# main.net
KiCad netlist of a schematic drawn in EAGLE
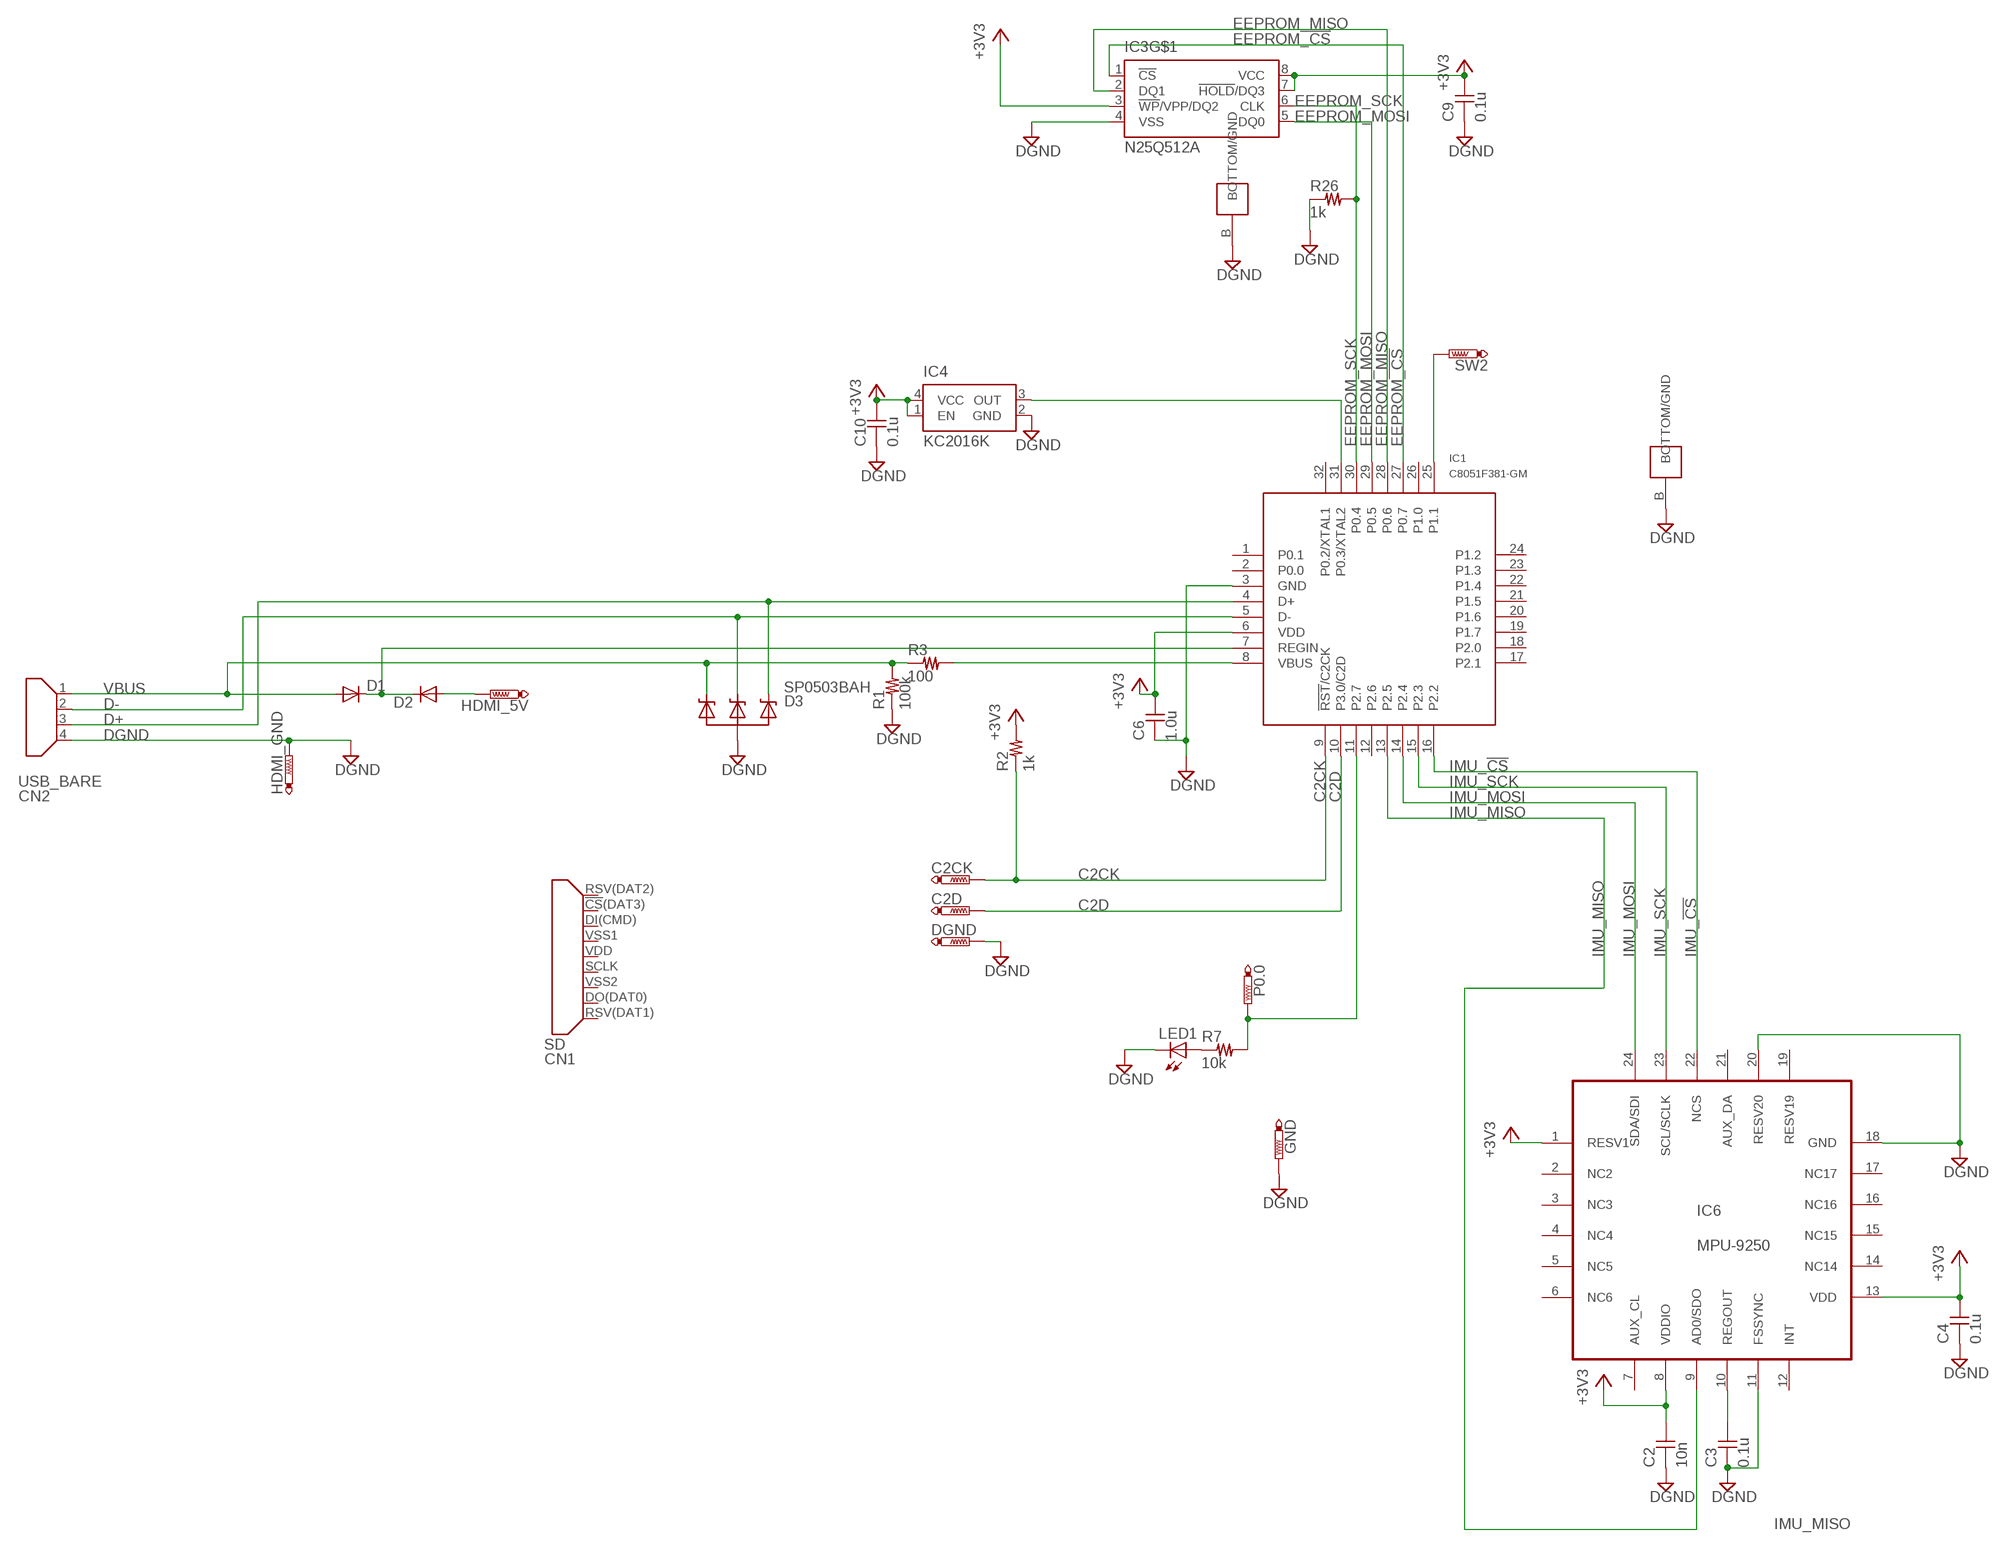
[diagram p0: schematic, sheet 1]

(export (version "E")
  (design (tool "Eeschema 10.0.6"))
  (components
    (comp (ref "C2")
      (value "10n")
      (footprint "eagle-import:1005")
      (libsource (lib "eagle-import") (part "C-1005"))
    )
    (comp (ref "C2CK")
      (value "PTR1TP10R")
      (footprint "eagle-import:TP10R")
      (libsource (lib "eagle-import") (part "PTR1TP10R"))
    )
    (comp (ref "C2D")
      (value "PTR1TP10R")
      (footprint "eagle-import:TP10R")
      (libsource (lib "eagle-import") (part "PTR1TP10R"))
    )
    (comp (ref "C3")
      (value "0.1u")
      (footprint "eagle-import:1005")
      (libsource (lib "eagle-import") (part "C-1005"))
    )
    (comp (ref "C4")
      (value "0.1u")
      (footprint "eagle-import:1005")
      (libsource (lib "eagle-import") (part "C-1005"))
    )
    (comp (ref "C6")
      (value "1.0u")
      (footprint "eagle-import:1005")
      (libsource (lib "eagle-import") (part "C-1005"))
    )
    (comp (ref "C9")
      (value "0.1u")
      (footprint "eagle-import:1005")
      (libsource (lib "eagle-import") (part "C-1005"))
    )
    (comp (ref "C10")
      (value "0.1u")
      (footprint "eagle-import:1005")
      (libsource (lib "eagle-import") (part "C-1005"))
    )
    (comp (ref "CN1") (value "SD") (footprint "eagle-import:SD") (libsource (lib "eagle-import") (part "SD")))
    (comp (ref "CN2")
      (value "USB_BARE")
      (footprint "eagle-import:USB_BARE")
      (libsource (lib "eagle-import") (part "USB_BARE"))
    )
    (comp (ref "D1")
      (value "DIODE-SOD323-W")
      (footprint "eagle-import:SOD323-W")
      (libsource (lib "eagle-import") (part "DIODE-SOD323-W"))
    )
    (comp (ref "D2")
      (value "DIODE-SOD323-W")
      (footprint "eagle-import:SOD323-W")
      (libsource (lib "eagle-import") (part "DIODE-SOD323-W"))
    )
    (comp (ref "D3")
      (value "SP0503BAH")
      (footprint "eagle-import:SOT143")
      (libsource (lib "eagle-import") (part "SP0503BAH"))
    )
    (comp (ref "DGND")
      (value "PTR1TP10R")
      (footprint "eagle-import:TP10R")
      (libsource (lib "eagle-import") (part "PTR1TP10R"))
    )
    (comp (ref "GND")
      (value "PTR1TP10R")
      (footprint "eagle-import:TP10R")
      (libsource (lib "eagle-import") (part "PTR1TP10R"))
    )
    (comp (ref "HDMI_5V")
      (value "PTR1TP11R")
      (footprint "eagle-import:TP11R")
      (libsource (lib "eagle-import") (part "PTR1TP11R"))
    )
    (comp (ref "HDMI_GND")
      (value "PTR1TP11R")
      (footprint "eagle-import:TP11R")
      (libsource (lib "eagle-import") (part "PTR1TP11R"))
    )
    (comp (ref "IC1")
      (value "C8051F381-GM")
      (footprint "eagle-import:QFN32")
      (libsource (lib "eagle-import") (part "C8051F381-GM"))
    )
    (comp (ref "IC3")
      (value "N25Q512A")
      (footprint "eagle-import:V-PDFN-8")
      (libsource (lib "eagle-import") (part "N25Q512A"))
    )
    (comp (ref "IC4")
      (value "KC2016K")
      (footprint "eagle-import:KC2016K")
      (libsource (lib "eagle-import") (part "KC2016K"))
    )
    (comp (ref "IC6")
      (value "MPU-9250")
      (footprint "eagle-import:QFN-24")
      (libsource (lib "eagle-import") (part "MPU-9250"))
    )
    (comp (ref "LED1")
      (value "LED1608O")
      (footprint "eagle-import:1608-OLI")
      (libsource (lib "eagle-import") (part "LED1608O"))
    )
    (comp (ref "P0.0")
      (value "PTR1TP10R")
      (footprint "eagle-import:TP10R")
      (libsource (lib "eagle-import") (part "PTR1TP10R"))
    )
    (comp (ref "R1")
      (value "100k")
      (footprint "eagle-import:1005")
      (libsource (lib "eagle-import") (part "R-1005"))
    )
    (comp (ref "R2")
      (value "1k")
      (footprint "eagle-import:1005")
      (libsource (lib "eagle-import") (part "R-1005"))
    )
    (comp (ref "R3")
      (value "100")
      (footprint "eagle-import:1005")
      (libsource (lib "eagle-import") (part "R-1005"))
    )
    (comp (ref "R7")
      (value "10k")
      (footprint "eagle-import:1005")
      (libsource (lib "eagle-import") (part "R-1005"))
    )
    (comp (ref "R26")
      (value "1k")
      (footprint "eagle-import:1005")
      (libsource (lib "eagle-import") (part "R-1005"))
    )
    (comp (ref "SW2")
      (value "PTR1TP10R")
      (footprint "eagle-import:TP10R")
      (libsource (lib "eagle-import") (part "PTR1TP10R"))
    )
  )
  (nets
    (net (code "1") (name "+3V3") (class "Default")
      (node (ref "C10") (pin "P$2") (pinfunction "P$2_P$2") (pintype "passive"))
      (node (ref "C2") (pin "P$2") (pinfunction "P$2_P$2") (pintype "passive"))
      (node (ref "C4") (pin "P$2") (pinfunction "P$2_P$2") (pintype "passive"))
      (node (ref "C6") (pin "P$2") (pinfunction "P$2_P$2") (pintype "passive"))
      (node (ref "C9") (pin "P$2") (pinfunction "P$2_P$2") (pintype "passive"))
      (node (ref "IC1") (pin "6") (pinfunction "VDD_6") (pintype "bidirectional"))
      (node (ref "IC3") (pin "3") (pinfunction "~{WP}/VPP/DQ2_3") (pintype "bidirectional"))
      (node (ref "IC3") (pin "7") (pinfunction "~{HOLD}/DQ3_7") (pintype "bidirectional"))
      (node (ref "IC3") (pin "8") (pinfunction "VCC_8") (pintype "power_in"))
      (node (ref "IC4") (pin "1") (pinfunction "EN_1") (pintype "input"))
      (node (ref "IC4") (pin "4") (pinfunction "VCC_4") (pintype "power_in"))
      (node (ref "IC6") (pin "1") (pinfunction "RESV1_1") (pintype "input"))
      (node (ref "IC6") (pin "13") (pinfunction "VDD_13") (pintype "power_in"))
      (node (ref "IC6") (pin "8") (pinfunction "VDDIO_8") (pintype "power_in"))
      (node (ref "R2") (pin "P$2") (pinfunction "P$2_P$2") (pintype "passive"))
    )
    (net (code "2") (name "/C2CK") (class "Default")
      (node (ref "C2CK") (pin "TP") (pinfunction "TP_TP") (pintype "input"))
      (node (ref "IC1") (pin "9") (pinfunction "~{RST}/C2CK_9") (pintype "bidirectional"))
      (node (ref "R2") (pin "P$1") (pinfunction "P$1_P$1") (pintype "passive"))
    )
    (net (code "3") (name "/C2D") (class "Default")
      (node (ref "C2D") (pin "TP") (pinfunction "TP_TP") (pintype "input"))
      (node (ref "IC1") (pin "10") (pinfunction "P3.0/C2D_10") (pintype "bidirectional"))
    )
    (net (code "4") (name "/D+") (class "Default")
      (node (ref "CN2") (pin "3") (pinfunction "P$3_3") (pintype "passive"))
      (node (ref "D3") (pin "2") (pinfunction "2_2") (pintype "passive"))
      (node (ref "IC1") (pin "4") (pinfunction "D+_4") (pintype "bidirectional"))
    )
    (net (code "5") (name "/D-") (class "Default")
      (node (ref "CN2") (pin "2") (pinfunction "P$2_2") (pintype "passive"))
      (node (ref "D3") (pin "3") (pinfunction "3_3") (pintype "passive"))
      (node (ref "IC1") (pin "5") (pinfunction "D-_5") (pintype "bidirectional"))
    )
    (net (code "6") (name "/EEPROM_MISO") (class "Default")
      (node (ref "IC1") (pin "28") (pinfunction "P0.6_28") (pintype "bidirectional"))
      (node (ref "IC3") (pin "2") (pinfunction "DQ1_2") (pintype "bidirectional"))
    )
    (net (code "7") (name "/EEPROM_MOSI") (class "Default")
      (node (ref "IC1") (pin "29") (pinfunction "P0.5_29") (pintype "bidirectional"))
      (node (ref "IC3") (pin "5") (pinfunction "DQ0_5") (pintype "bidirectional"))
    )
    (net (code "8") (name "/EEPROM_SCK") (class "Default")
      (node (ref "IC1") (pin "30") (pinfunction "P0.4_30") (pintype "bidirectional"))
      (node (ref "IC3") (pin "6") (pinfunction "CLK_6") (pintype "input"))
      (node (ref "R26") (pin "P$2") (pinfunction "P$2_P$2") (pintype "passive"))
    )
    (net (code "9") (name "/EEPROM_~{CS}") (class "Default")
      (node (ref "IC1") (pin "27") (pinfunction "P0.7_27") (pintype "bidirectional"))
      (node (ref "IC3") (pin "1") (pinfunction "~{CS}_1") (pintype "input"))
    )
    (net (code "10") (name "/IMU_MISO") (class "Default")
      (node (ref "IC1") (pin "13") (pinfunction "P2.5_13") (pintype "bidirectional"))
      (node (ref "IC6") (pin "9") (pinfunction "AD0/SDO_9") (pintype "bidirectional"))
    )
    (net (code "11") (name "/IMU_MOSI") (class "Default")
      (node (ref "IC1") (pin "14") (pinfunction "P2.4_14") (pintype "bidirectional"))
      (node (ref "IC6") (pin "24") (pinfunction "SDA/SDI_24") (pintype "input"))
    )
    (net (code "12") (name "/IMU_SCK") (class "Default")
      (node (ref "IC1") (pin "15") (pinfunction "P2.3_15") (pintype "bidirectional"))
      (node (ref "IC6") (pin "23") (pinfunction "SCL/SCLK_23") (pintype "input"))
    )
    (net (code "13") (name "/IMU_~{CS}") (class "Default")
      (node (ref "IC1") (pin "16") (pinfunction "P2.2_16") (pintype "bidirectional"))
      (node (ref "IC6") (pin "22") (pinfunction "NCS_22") (pintype "input"))
    )
    (net (code "14") (name "/VBUS") (class "Default")
      (node (ref "CN2") (pin "1") (pinfunction "P$1_1") (pintype "passive"))
      (node (ref "D1") (pin "A") (pinfunction "A_A") (pintype "passive"))
      (node (ref "D3") (pin "4") (pinfunction "4_4") (pintype "passive"))
      (node (ref "R1") (pin "P$2") (pinfunction "P$2_P$2") (pintype "passive"))
      (node (ref "R3") (pin "P$1") (pinfunction "P$1_P$1") (pintype "passive"))
    )
    (net (code "15") (name "DGND") (class "Default")
      (node (ref "C10") (pin "P$1") (pinfunction "P$1_P$1") (pintype "passive"))
      (node (ref "C2") (pin "P$1") (pinfunction "P$1_P$1") (pintype "passive"))
      (node (ref "C3") (pin "P$1") (pinfunction "P$1_P$1") (pintype "passive"))
      (node (ref "C4") (pin "P$1") (pinfunction "P$1_P$1") (pintype "passive"))
      (node (ref "C6") (pin "P$1") (pinfunction "P$1_P$1") (pintype "passive"))
      (node (ref "C9") (pin "P$1") (pinfunction "P$1_P$1") (pintype "passive"))
      (node (ref "CN2") (pin "4") (pinfunction "P$4_4") (pintype "passive"))
      (node (ref "D3") (pin "1") (pinfunction "1_1") (pintype "passive"))
      (node (ref "DGND") (pin "TP") (pinfunction "TP_TP") (pintype "input"))
      (node (ref "GND") (pin "TP") (pinfunction "TP_TP") (pintype "input"))
      (node (ref "HDMI_GND") (pin "TP") (pinfunction "TP_TP") (pintype "input"))
      (node (ref "IC1") (pin "3") (pinfunction "GND_3") (pintype "bidirectional"))
      (node (ref "IC1") (pin "B") (pinfunction "BOTTOM/GND_B") (pintype "power_in"))
      (node (ref "IC3") (pin "4") (pinfunction "VSS_4") (pintype "power_in"))
      (node (ref "IC3") (pin "B") (pinfunction "BOTTOM/GND_B") (pintype "power_in"))
      (node (ref "IC4") (pin "2") (pinfunction "GND_2") (pintype "power_in"))
      (node (ref "IC6") (pin "11") (pinfunction "FSSYNC_11") (pintype "input"))
      (node (ref "IC6") (pin "18") (pinfunction "GND_18") (pintype "power_in"))
      (node (ref "IC6") (pin "20") (pinfunction "RESV20_20") (pintype "input"))
      (node (ref "LED1") (pin "K") (pinfunction "K_K") (pintype "passive"))
      (node (ref "R1") (pin "P$1") (pinfunction "P$1_P$1") (pintype "passive"))
      (node (ref "R26") (pin "P$1") (pinfunction "P$1_P$1") (pintype "passive"))
    )
    (net (code "16") (name "Net-(D2-PadA)") (class "Default")
      (node (ref "D2") (pin "A") (pinfunction "A_A") (pintype "passive"))
      (node (ref "HDMI_5V") (pin "TP") (pinfunction "TP_TP") (pintype "input"))
    )
    (net (code "17") (name "Net-(IC1A-P0.3{slash}XTAL2)") (class "Default")
      (node (ref "IC1") (pin "31") (pinfunction "P0.3/XTAL2_31") (pintype "bidirectional"))
      (node (ref "IC4") (pin "3") (pinfunction "OUT_3") (pintype "output"))
    )
    (net (code "18") (name "Net-(IC1A-P1.1)") (class "Default")
      (node (ref "IC1") (pin "25") (pinfunction "P1.1_25") (pintype "bidirectional"))
      (node (ref "SW2") (pin "TP") (pinfunction "TP_TP") (pintype "input"))
    )
    (net (code "19") (name "Net-(IC1A-P2.7)") (class "Default")
      (node (ref "IC1") (pin "11") (pinfunction "P2.7_11") (pintype "bidirectional"))
      (node (ref "P0.0") (pin "TP") (pinfunction "TP_TP") (pintype "input"))
      (node (ref "R7") (pin "P$2") (pinfunction "P$2_P$2") (pintype "passive"))
    )
    (net (code "20") (name "Net-(IC1A-REGIN)") (class "Default")
      (node (ref "D1") (pin "C") (pinfunction "C_C") (pintype "passive"))
      (node (ref "D2") (pin "C") (pinfunction "C_C") (pintype "passive"))
      (node (ref "IC1") (pin "7") (pinfunction "REGIN_7") (pintype "bidirectional"))
    )
    (net (code "21") (name "Net-(IC1A-VBUS)") (class "Default")
      (node (ref "IC1") (pin "8") (pinfunction "VBUS_8") (pintype "bidirectional"))
      (node (ref "R3") (pin "P$2") (pinfunction "P$2_P$2") (pintype "passive"))
    )
    (net (code "22") (name "Net-(IC6-REGOUT)") (class "Default")
      (node (ref "C3") (pin "P$2") (pinfunction "P$2_P$2") (pintype "passive"))
      (node (ref "IC6") (pin "10") (pinfunction "REGOUT_10") (pintype "bidirectional"))
    )
    (net (code "23") (name "Net-(LED1-PadA)") (class "Default")
      (node (ref "LED1") (pin "A") (pinfunction "A_A") (pintype "passive"))
      (node (ref "R7") (pin "P$1") (pinfunction "P$1_P$1") (pintype "passive"))
    )
    (net (code "24") (name "unconnected-(CN1-P$1-PadRSV(DAT2))") (class "Default")
      (node (ref "CN1") (pin "RSV(DAT2)") (pinfunction "P$1_RSV(DAT2)") (pintype "passive"))
    )
    (net (code "25") (name "unconnected-(CN1-P$2-Pad!CS!(DAT3))") (class "Default")
      (node (ref "CN1") (pin "!CS!(DAT3)") (pinfunction "P$2_!CS!(DAT3)") (pintype "passive"))
    )
    (net (code "26") (name "unconnected-(CN1-P$3-PadDI(CMD))") (class "Default")
      (node (ref "CN1") (pin "DI(CMD)") (pinfunction "P$3_DI(CMD)") (pintype "passive"))
    )
    (net (code "27") (name "unconnected-(CN1-P$4-PadVSS1)") (class "Default")
      (node (ref "CN1") (pin "VSS1") (pinfunction "P$4_VSS1") (pintype "passive"))
    )
    (net (code "28") (name "unconnected-(CN1-P$5-PadVDD)") (class "Default")
      (node (ref "CN1") (pin "VDD") (pinfunction "P$5_VDD") (pintype "passive"))
    )
    (net (code "29") (name "unconnected-(CN1-P$6-PadSCLK)") (class "Default")
      (node (ref "CN1") (pin "SCLK") (pinfunction "P$6_SCLK") (pintype "passive"))
    )
    (net (code "30") (name "unconnected-(CN1-P$7-PadVSS2)") (class "Default")
      (node (ref "CN1") (pin "VSS2") (pinfunction "P$7_VSS2") (pintype "passive"))
    )
    (net (code "31") (name "unconnected-(CN1-P$8-PadDO(DAT0))") (class "Default")
      (node (ref "CN1") (pin "DO(DAT0)") (pinfunction "P$8_DO(DAT0)") (pintype "passive"))
    )
    (net (code "32") (name "unconnected-(CN1-P$9-PadRSV(DAT1))") (class "Default")
      (node (ref "CN1") (pin "RSV(DAT1)") (pinfunction "P$9_RSV(DAT1)") (pintype "passive"))
    )
    (net (code "33") (name "unconnected-(IC1A-P0.0-Pad2)") (class "Default")
      (node (ref "IC1") (pin "2") (pinfunction "P0.0_2") (pintype "bidirectional"))
    )
    (net (code "34") (name "unconnected-(IC1A-P0.1-Pad1)") (class "Default")
      (node (ref "IC1") (pin "1") (pinfunction "P0.1_1") (pintype "bidirectional"))
    )
    (net (code "35") (name "unconnected-(IC1A-P0.2{slash}XTAL1-Pad32)") (class "Default")
      (node (ref "IC1") (pin "32") (pinfunction "P0.2/XTAL1_32") (pintype "bidirectional"))
    )
    (net (code "36") (name "unconnected-(IC1A-P1.0-Pad26)") (class "Default")
      (node (ref "IC1") (pin "26") (pinfunction "P1.0_26") (pintype "bidirectional"))
    )
    (net (code "37") (name "unconnected-(IC1A-P1.2-Pad24)") (class "Default")
      (node (ref "IC1") (pin "24") (pinfunction "P1.2_24") (pintype "bidirectional"))
    )
    (net (code "38") (name "unconnected-(IC1A-P1.3-Pad23)") (class "Default")
      (node (ref "IC1") (pin "23") (pinfunction "P1.3_23") (pintype "bidirectional"))
    )
    (net (code "39") (name "unconnected-(IC1A-P1.4-Pad22)") (class "Default")
      (node (ref "IC1") (pin "22") (pinfunction "P1.4_22") (pintype "bidirectional"))
    )
    (net (code "40") (name "unconnected-(IC1A-P1.5-Pad21)") (class "Default")
      (node (ref "IC1") (pin "21") (pinfunction "P1.5_21") (pintype "bidirectional"))
    )
    (net (code "41") (name "unconnected-(IC1A-P1.6-Pad20)") (class "Default")
      (node (ref "IC1") (pin "20") (pinfunction "P1.6_20") (pintype "bidirectional"))
    )
    (net (code "42") (name "unconnected-(IC1A-P1.7-Pad19)") (class "Default")
      (node (ref "IC1") (pin "19") (pinfunction "P1.7_19") (pintype "bidirectional"))
    )
    (net (code "43") (name "unconnected-(IC1A-P2.0-Pad18)") (class "Default")
      (node (ref "IC1") (pin "18") (pinfunction "P2.0_18") (pintype "bidirectional"))
    )
    (net (code "44") (name "unconnected-(IC1A-P2.1-Pad17)") (class "Default")
      (node (ref "IC1") (pin "17") (pinfunction "P2.1_17") (pintype "bidirectional"))
    )
    (net (code "45") (name "unconnected-(IC1A-P2.6-Pad12)") (class "Default")
      (node (ref "IC1") (pin "12") (pinfunction "P2.6_12") (pintype "bidirectional"))
    )
    (net (code "46") (name "unconnected-(IC6-AUX_CL-Pad7)") (class "Default")
      (node (ref "IC6") (pin "7") (pinfunction "AUX_CL_7") (pintype "output"))
    )
    (net (code "47") (name "unconnected-(IC6-AUX_DA-Pad21)") (class "Default")
      (node (ref "IC6") (pin "21") (pinfunction "AUX_DA_21") (pintype "bidirectional"))
    )
    (net (code "48") (name "unconnected-(IC6-INT-Pad12)") (class "Default")
      (node (ref "IC6") (pin "12") (pinfunction "INT_12") (pintype "output"))
    )
    (net (code "49") (name "unconnected-(IC6-NC2-Pad2)") (class "Default")
      (node (ref "IC6") (pin "2") (pinfunction "NC2_2") (pintype "no_connect"))
    )
    (net (code "50") (name "unconnected-(IC6-NC3-Pad3)") (class "Default")
      (node (ref "IC6") (pin "3") (pinfunction "NC3_3") (pintype "no_connect"))
    )
    (net (code "51") (name "unconnected-(IC6-NC4-Pad4)") (class "Default")
      (node (ref "IC6") (pin "4") (pinfunction "NC4_4") (pintype "no_connect"))
    )
    (net (code "52") (name "unconnected-(IC6-NC5-Pad5)") (class "Default")
      (node (ref "IC6") (pin "5") (pinfunction "NC5_5") (pintype "no_connect"))
    )
    (net (code "53") (name "unconnected-(IC6-NC6-Pad6)") (class "Default")
      (node (ref "IC6") (pin "6") (pinfunction "NC6_6") (pintype "no_connect"))
    )
    (net (code "54") (name "unconnected-(IC6-NC14-Pad14)") (class "Default")
      (node (ref "IC6") (pin "14") (pinfunction "NC14_14") (pintype "no_connect"))
    )
    (net (code "55") (name "unconnected-(IC6-NC15-Pad15)") (class "Default")
      (node (ref "IC6") (pin "15") (pinfunction "NC15_15") (pintype "no_connect"))
    )
    (net (code "56") (name "unconnected-(IC6-NC16-Pad16)") (class "Default")
      (node (ref "IC6") (pin "16") (pinfunction "NC16_16") (pintype "no_connect"))
    )
    (net (code "57") (name "unconnected-(IC6-NC17-Pad17)") (class "Default")
      (node (ref "IC6") (pin "17") (pinfunction "NC17_17") (pintype "no_connect"))
    )
    (net (code "58") (name "unconnected-(IC6-RESV19-Pad19)") (class "Default")
      (node (ref "IC6") (pin "19") (pinfunction "RESV19_19") (pintype "no_connect"))
    )
  )
)
